# ClubNIKA.net
KiCad netlist of a schematic drawn in Altium Designer
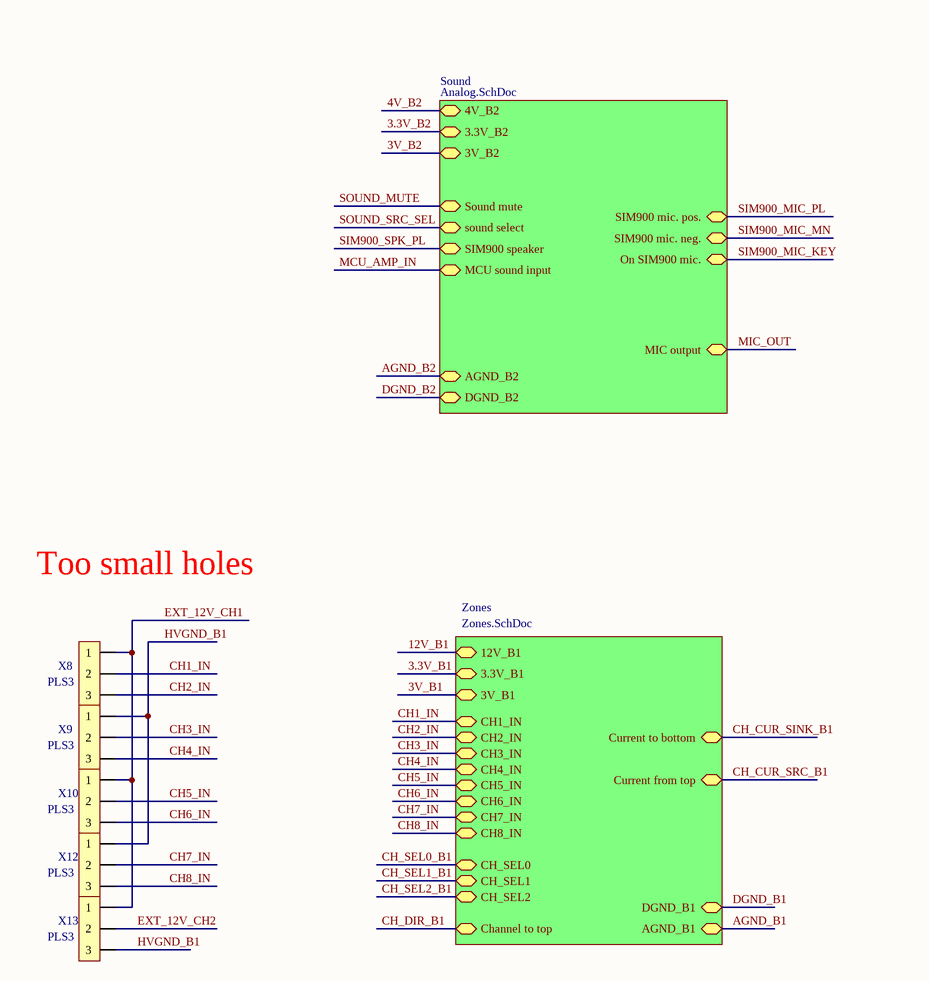
[diagram p0: ClubNIKA.SchDoc, top left]
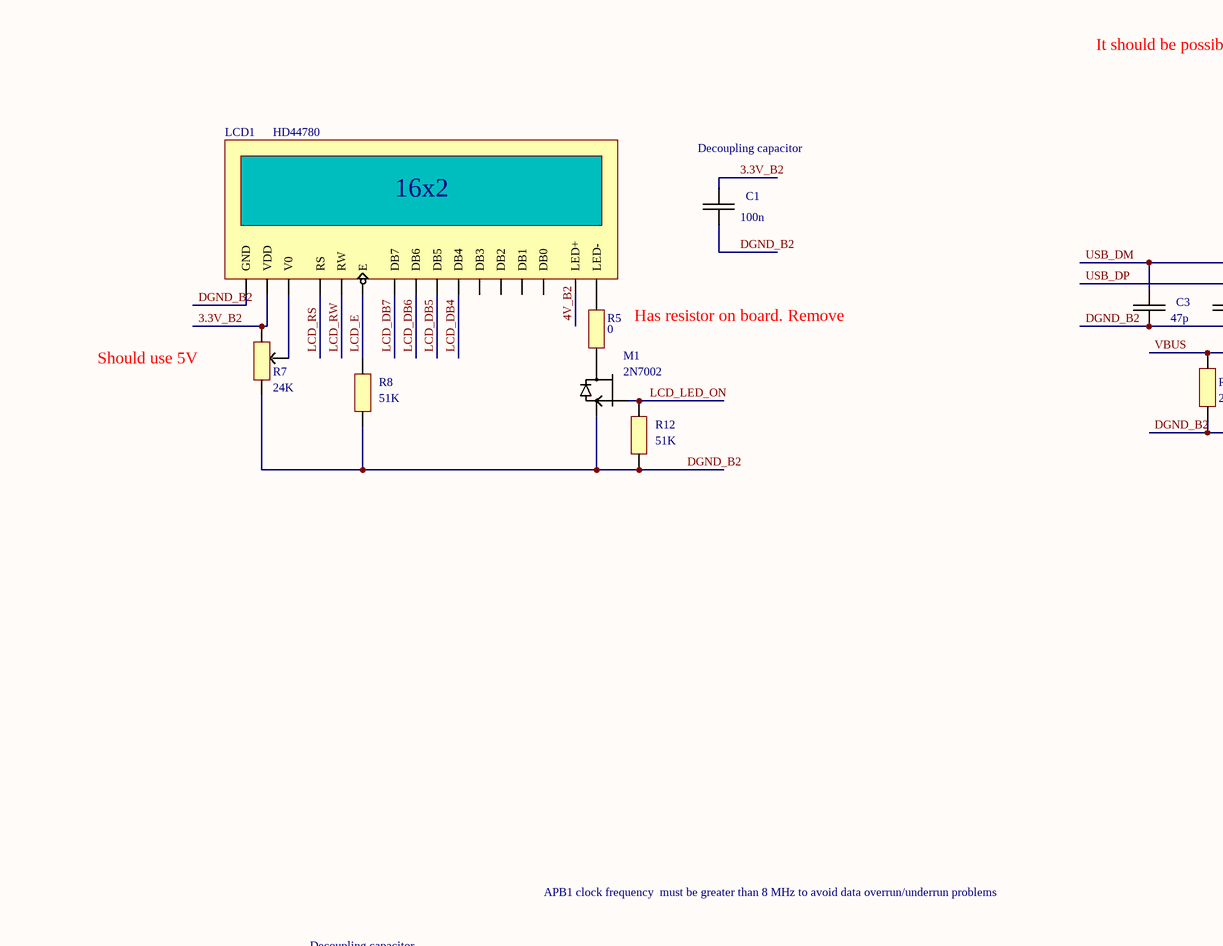
[diagram p1: ClubNIKA.SchDoc, top middle]
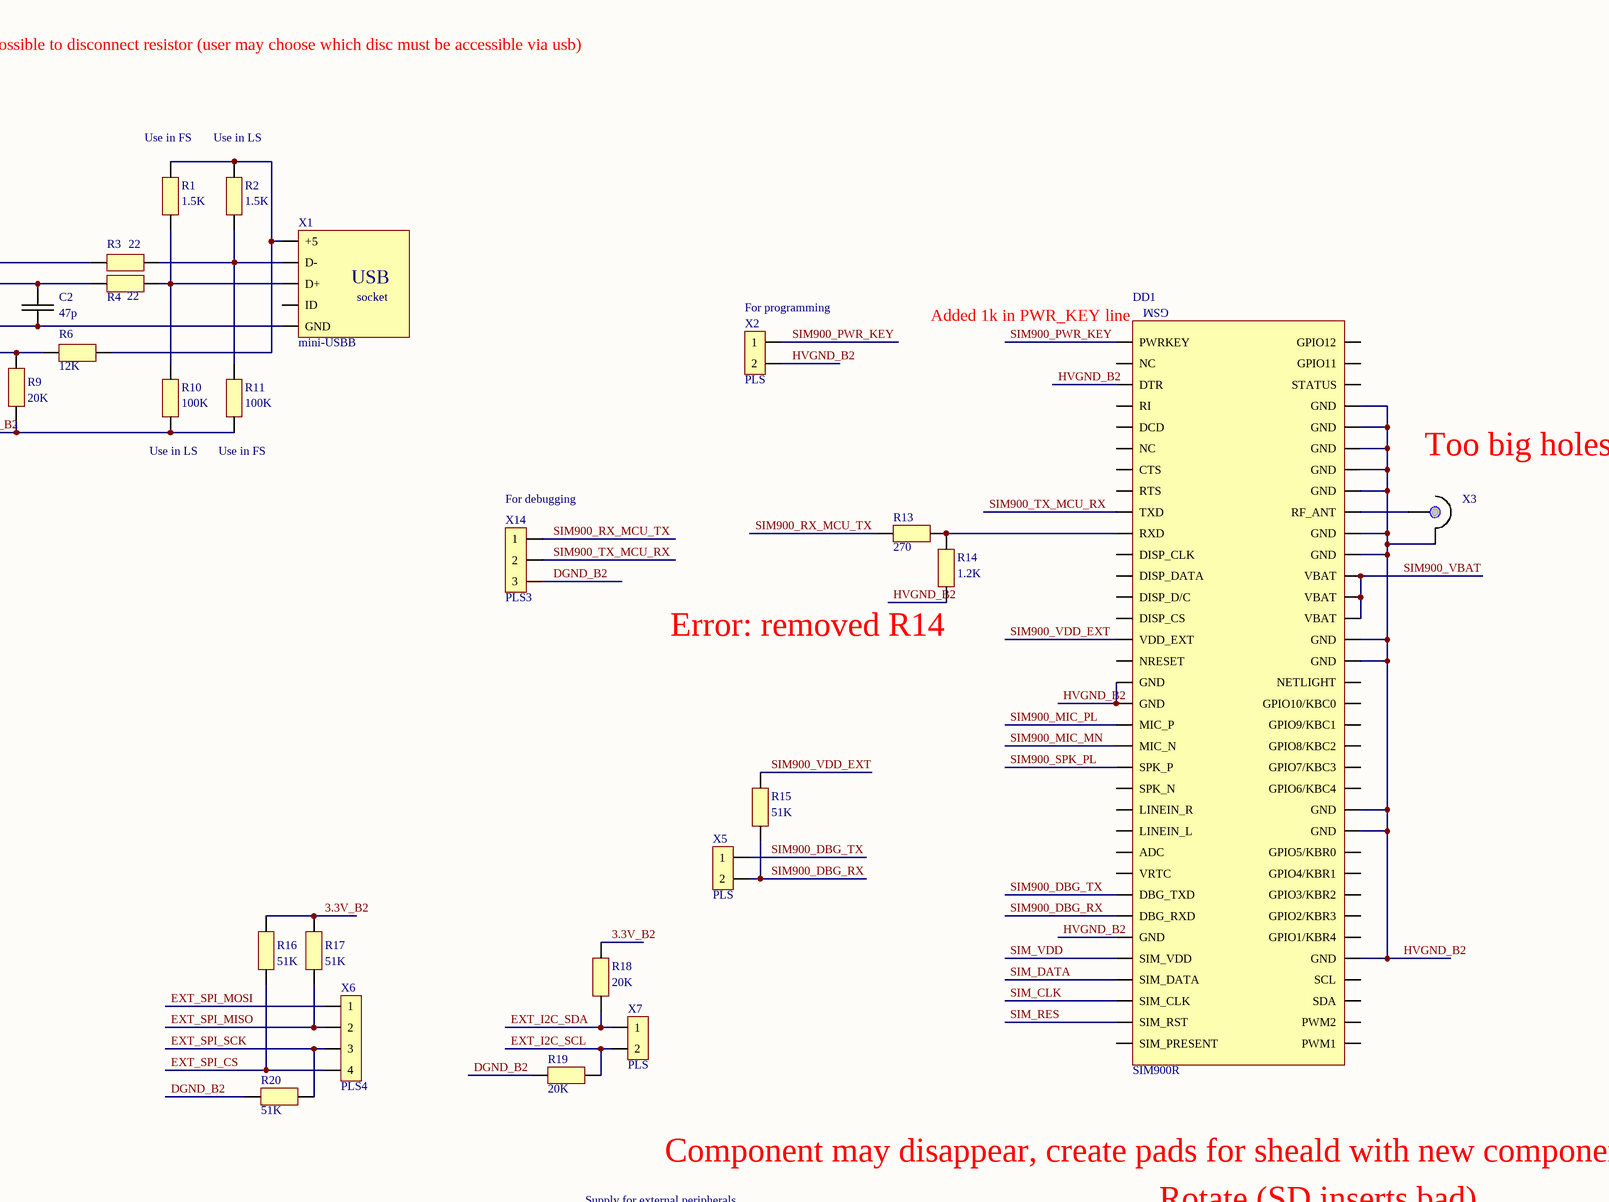
[diagram p2: ClubNIKA.SchDoc, top right]
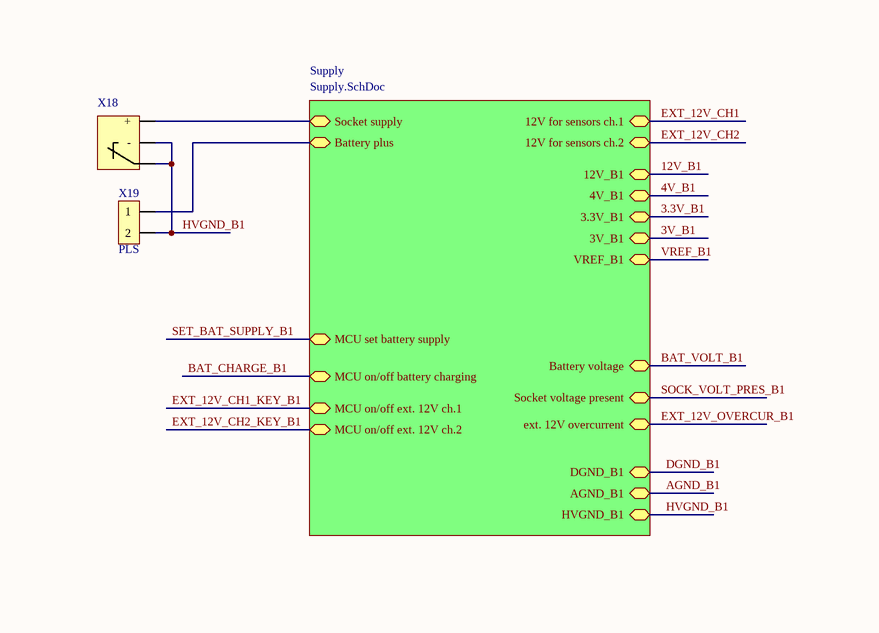
[diagram p3: ClubNIKA.SchDoc, bottom left]
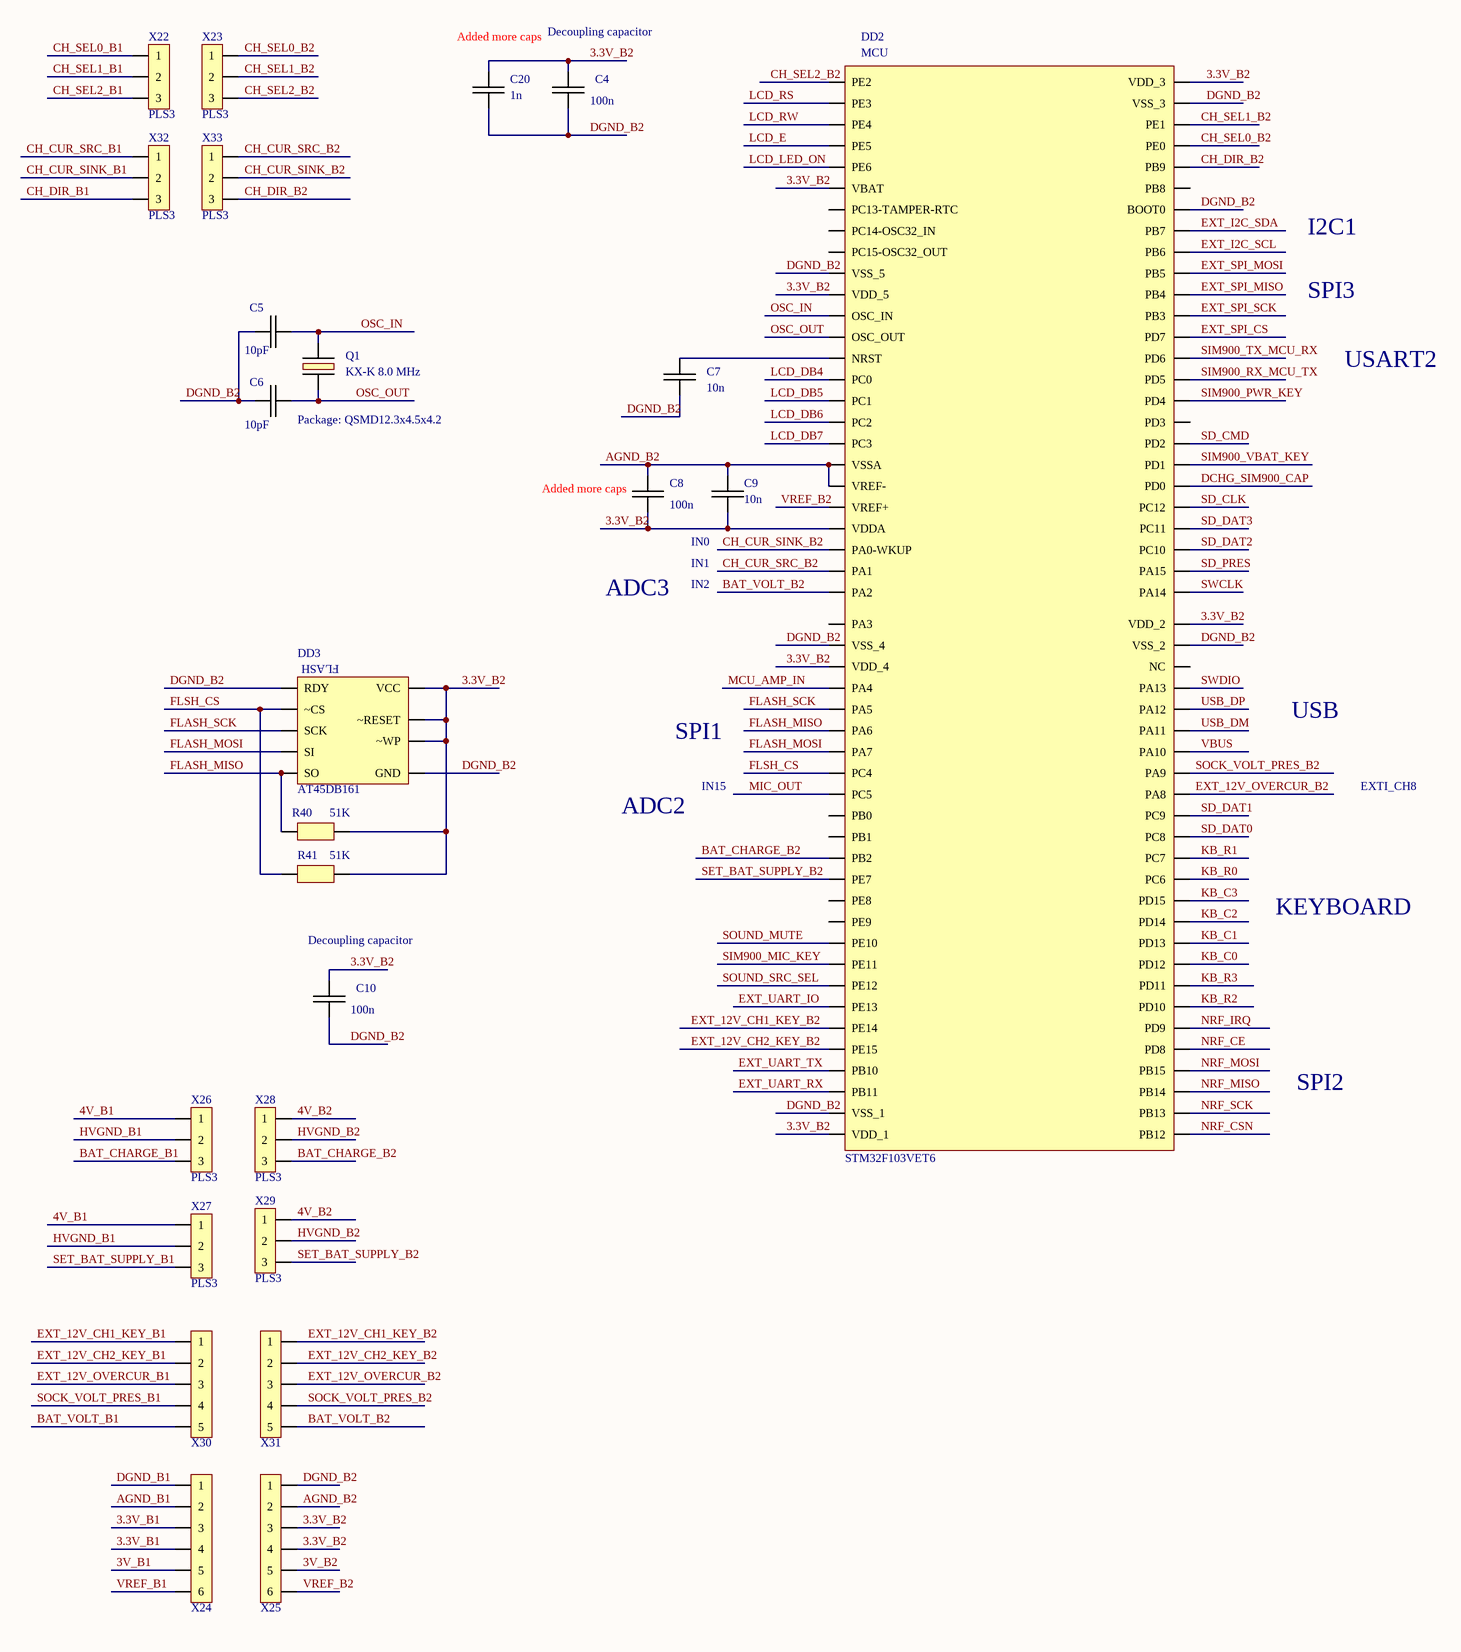
[diagram p4: ClubNIKA.SchDoc, bottom middle]
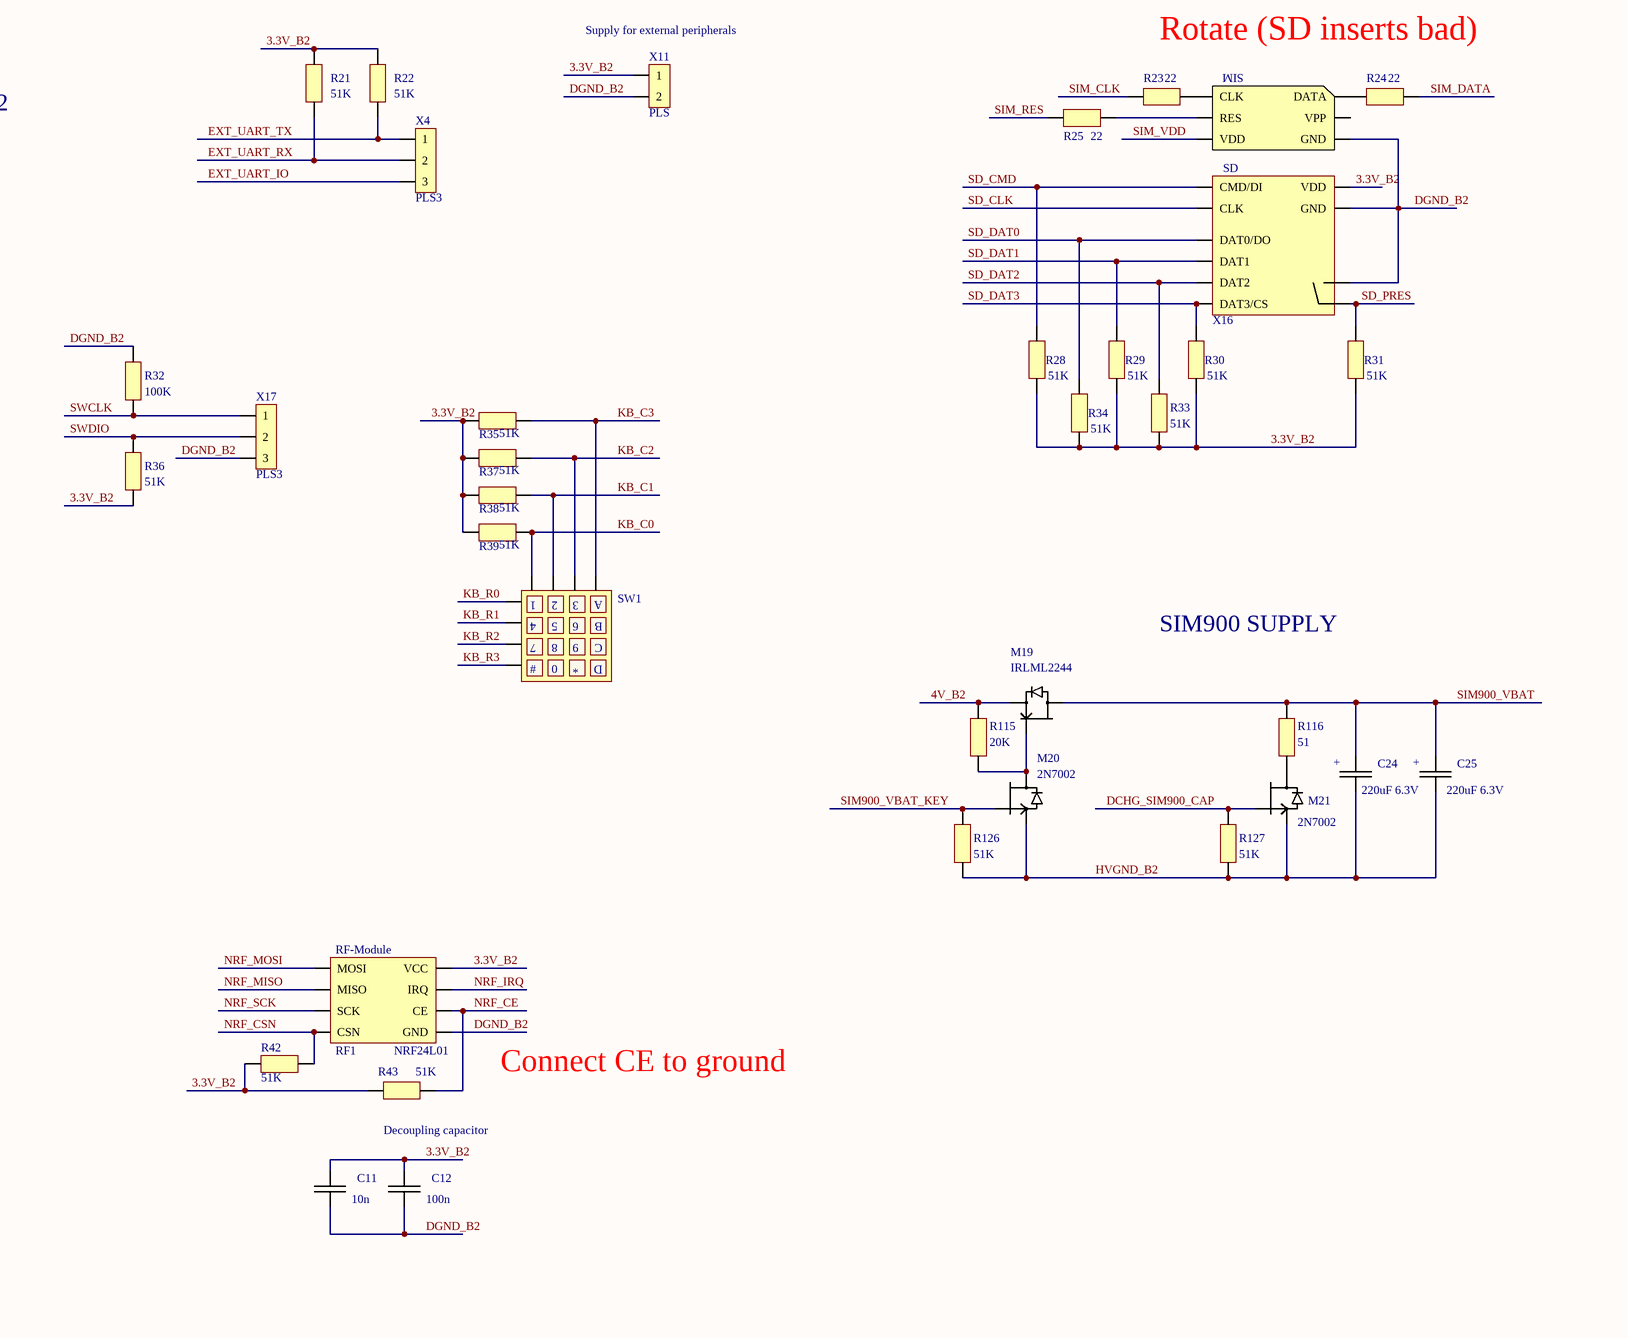
[diagram p5: ClubNIKA.SchDoc, bottom right]

(export (version "E")
  (design (tool "Eeschema 10.0.6"))
  (components
    (comp (ref "C1") (value "100n") (footprint "0805") (libsource (lib "PRIM_fact") (part "C")))
    (comp (ref "C2") (value "47p") (footprint "0805") (libsource (lib "PRIM_fact") (part "C")))
    (comp (ref "C3") (value "47p") (footprint "0805") (libsource (lib "PRIM_fact") (part "C")))
    (comp (ref "C4") (value "100n") (footprint "0805") (libsource (lib "PRIM_fact") (part "C")))
    (comp (ref "C5") (value "10pF") (footprint "0805") (libsource (lib "PRIM_fact") (part "C")))
    (comp (ref "C6") (value "10pF") (footprint "0805") (libsource (lib "PRIM_fact") (part "C")))
    (comp (ref "C7") (value "10n") (footprint "0805") (libsource (lib "PRIM_fact") (part "C")))
    (comp (ref "C8") (value "100n") (footprint "0805") (libsource (lib "PRIM_fact") (part "C")))
    (comp (ref "C9") (value "10n") (footprint "0805") (libsource (lib "PRIM_fact") (part "C")))
    (comp (ref "C10") (value "100n") (footprint "0805") (libsource (lib "PRIM_fact") (part "C")))
    (comp (ref "C11") (value "10n") (footprint "0805") (libsource (lib "PRIM_fact") (part "C")))
    (comp (ref "C12") (value "100n") (footprint "0805") (libsource (lib "PRIM_fact") (part "C")))
    (comp (ref "C20") (value "1n") (footprint "0805") (libsource (lib "PRIM_fact") (part "C")))
    (comp (ref "C24")
      (value "220uF 6.3V")
      (footprint "CALUM_THT_E5D13")
      (libsource (lib "PRIM_fact") (part "C_POL"))
    )
    (comp (ref "C25")
      (value "220uF 6.3V")
      (footprint "CALUM_THT_E5D13")
      (libsource (lib "PRIM_fact") (part "C_POL"))
    )
    (comp (ref "DD1") (value "SIM900R") (footprint "SIM900_R") (libsource (lib "IC_fact") (part "SIM900R")))
    (comp (ref "DD2")
      (value "STM32F103VET6")
      (footprint "QFP100")
      (libsource (lib "IC_fact") (part "STM32F103Vx"))
    )
    (comp (ref "DD3")
      (value "AT45DB161")
      (footprint "TSOP28")
      (libsource (lib "IC_fact") (part "AT45DB161/321"))
    )
    (comp (ref "LCD1")
      (value "HD44780")
      (footprint "LCD_HD44780_5")
      (libsource (lib "IC_fact") (part "LCD 16x2 HD44780"))
    )
    (comp (ref "M1") (value "2N7002") (footprint "SOT-23") (libsource (lib "PRIM_fact") (part "NMOS+DIODE")))
    (comp (ref "M19")
      (value "IRLML2244")
      (footprint "SOT-23")
      (libsource (lib "PRIM_fact") (part "PMOS+DIODE"))
    )
    (comp (ref "M20") (value "2N7002") (footprint "SOT-23") (libsource (lib "PRIM_fact") (part "NMOS+DIODE")))
    (comp (ref "M21") (value "2N7002") (footprint "SOT-23") (libsource (lib "PRIM_fact") (part "NMOS+DIODE")))
    (comp (ref "Q1")
      (value "KX-K 8.0 MHz")
      (footprint "OSC1_THT_10,8x4,5")
      (libsource (lib "PRIM_fact") (part "XTAL"))
    )
    (comp (ref "R1") (value "1.5K") (footprint "0805") (libsource (lib "PRIM_fact") (part "R")))
    (comp (ref "R2") (value "1.5K") (footprint "0805") (libsource (lib "PRIM_fact") (part "R")))
    (comp (ref "R3") (value "22") (footprint "0805") (libsource (lib "") (part "R_1")))
    (comp (ref "R4") (value "22") (footprint "0805") (libsource (lib "") (part "R_1")))
    (comp (ref "R5") (value "0") (footprint "1206") (libsource (lib "PRIM_fact") (part "R")))
    (comp (ref "R6") (value "12K") (footprint "0805") (libsource (lib "") (part "R_1")))
    (comp (ref "R7") (value "24K") (footprint "3305SMD(adj res)") (libsource (lib "PRIM_fact") (part "Radj")))
    (comp (ref "R8") (value "51K") (footprint "0805") (libsource (lib "PRIM_fact") (part "R")))
    (comp (ref "R9") (value "20K") (footprint "0805") (libsource (lib "PRIM_fact") (part "R")))
    (comp (ref "R10") (value "100K") (footprint "0805") (libsource (lib "PRIM_fact") (part "R")))
    (comp (ref "R11") (value "100K") (footprint "0805") (libsource (lib "PRIM_fact") (part "R")))
    (comp (ref "R12") (value "51K") (footprint "0805") (libsource (lib "PRIM_fact") (part "R")))
    (comp (ref "R13") (value "270") (footprint "0805") (libsource (lib "") (part "R_2")))
    (comp (ref "R14") (value "1.2K") (footprint "0805") (libsource (lib "PRIM_fact") (part "R")))
    (comp (ref "R15") (value "51K") (footprint "0805") (libsource (lib "PRIM_fact") (part "R")))
    (comp (ref "R16") (value "51K") (footprint "0805") (libsource (lib "PRIM_fact") (part "R")))
    (comp (ref "R17") (value "51K") (footprint "0805") (libsource (lib "PRIM_fact") (part "R")))
    (comp (ref "R18") (value "20K") (footprint "0805") (libsource (lib "PRIM_fact") (part "R")))
    (comp (ref "R19") (value "20K") (footprint "0805") (libsource (lib "") (part "R_2")))
    (comp (ref "R20") (value "51K") (footprint "0805") (libsource (lib "") (part "R_2")))
    (comp (ref "R21") (value "51K") (footprint "0805") (libsource (lib "PRIM_fact") (part "R")))
    (comp (ref "R22") (value "51K") (footprint "0805") (libsource (lib "PRIM_fact") (part "R")))
    (comp (ref "R23") (value "22") (footprint "0805") (libsource (lib "") (part "R_1")))
    (comp (ref "R24") (value "22") (footprint "0805") (libsource (lib "") (part "R_1")))
    (comp (ref "R25") (value "22") (footprint "0805") (libsource (lib "") (part "R_1")))
    (comp (ref "R28") (value "51K") (footprint "0805") (libsource (lib "PRIM_fact") (part "R")))
    (comp (ref "R29") (value "51K") (footprint "0805") (libsource (lib "PRIM_fact") (part "R")))
    (comp (ref "R30") (value "51K") (footprint "0805") (libsource (lib "PRIM_fact") (part "R")))
    (comp (ref "R31") (value "51K") (footprint "0805") (libsource (lib "PRIM_fact") (part "R")))
    (comp (ref "R32") (value "100K") (footprint "0805") (libsource (lib "PRIM_fact") (part "R")))
    (comp (ref "R33") (value "51K") (footprint "0805") (libsource (lib "PRIM_fact") (part "R")))
    (comp (ref "R34") (value "51K") (footprint "0805") (libsource (lib "PRIM_fact") (part "R")))
    (comp (ref "R35") (value "51K") (footprint "0805") (libsource (lib "") (part "R_1")))
    (comp (ref "R36") (value "51K") (footprint "0805") (libsource (lib "PRIM_fact") (part "R")))
    (comp (ref "R37") (value "51K") (footprint "0805") (libsource (lib "") (part "R_1")))
    (comp (ref "R38") (value "51K") (footprint "0805") (libsource (lib "") (part "R_1")))
    (comp (ref "R39") (value "51K") (footprint "0805") (libsource (lib "") (part "R_1")))
    (comp (ref "R40") (value "51K") (footprint "0805") (libsource (lib "") (part "R_2")))
    (comp (ref "R41") (value "51K") (footprint "0805") (libsource (lib "") (part "R_2")))
    (comp (ref "R42") (value "51K") (footprint "0805") (libsource (lib "") (part "R_2")))
    (comp (ref "R43") (value "51K") (footprint "0805") (libsource (lib "") (part "R_1")))
    (comp (ref "R115") (value "20K") (footprint "0805") (libsource (lib "PRIM_fact") (part "R")))
    (comp (ref "R116") (value "51") (footprint "0805") (libsource (lib "PRIM_fact") (part "R")))
    (comp (ref "R126") (value "51K") (footprint "0805") (libsource (lib "") (part "R_1")))
    (comp (ref "R127") (value "51K") (footprint "0805") (libsource (lib "") (part "R_1")))
    (comp (ref "RF1")
      (value "NRF24L01")
      (footprint "NRF24L01_MOD_ANGLE")
      (libsource (lib "IC_fact") (part "NRF24L01"))
    )
    (comp (ref "SW1")
      (value "KEYBOARD4x4")
      (footprint "KEYBOURD_4x4_1")
      (libsource (lib "PRIM_fact") (part "KEYBOARD4x4"))
    )
    (comp (ref "X1")
      (value "mini-USBB")
      (footprint "MINI_USBA_FEMALE")
      (libsource (lib "PRIM_fact") (part "MINI_USB_FEMALE"))
    )
    (comp (ref "X2") (value "PLS") (footprint "PLS_2") (libsource (lib "") (part "CONT_2_1")))
    (comp (ref "X3")
      (value "SMA_FEMALE")
      (footprint "SMA_FEMALE")
      (libsource (lib "PRIM_fact") (part "SMA_FEMALE"))
    )
    (comp (ref "X4") (value "PLS3") (footprint "PLS_3") (libsource (lib "PRIM_fact") (part "CONT_3")))
    (comp (ref "X5") (value "PLS") (footprint "PLS_2") (libsource (lib "") (part "CONT_2_1")))
    (comp (ref "X6") (value "PLS4") (footprint "PLS_4") (libsource (lib "PRIM_fact") (part "CONT_4")))
    (comp (ref "X7") (value "PLS") (footprint "PLS_2") (libsource (lib "PRIM_fact") (part "CONT_2")))
    (comp (ref "X8")
      (value "PLS3")
      (footprint "TERMINALS_7.7x15.5(step 5mm)")
      (libsource (lib "") (part "CONT_3_1"))
    )
    (comp (ref "X9")
      (value "PLS3")
      (footprint "TERMINALS_7.7x15.5(step 5mm)")
      (libsource (lib "") (part "CONT_3_1"))
    )
    (comp (ref "X10")
      (value "PLS3")
      (footprint "TERMINALS_7.7x15.5(step 5mm)")
      (libsource (lib "") (part "CONT_3_1"))
    )
    (comp (ref "X11") (value "PLS") (footprint "PLS_2") (libsource (lib "PRIM_fact") (part "CONT_2")))
    (comp (ref "X12")
      (value "PLS3")
      (footprint "TERMINALS_7.7x15.5(step 5mm)")
      (libsource (lib "") (part "CONT_3_1"))
    )
    (comp (ref "X13")
      (value "PLS3")
      (footprint "TERMINALS_7.7x15.5(step 5mm)")
      (libsource (lib "") (part "CONT_3_1"))
    )
    (comp (ref "X14") (value "PLS3") (footprint "PLS_3") (libsource (lib "") (part "CONT_3_1")))
    (comp (ref "X16")
      (value "SIM_SD_HOLDER1")
      (footprint "SIM_SD_HOLDER1")
      (libsource (lib "PRIM_fact") (part "SIM_SD_HOLDER1"))
    )
    (comp (ref "X17") (value "PLS3") (footprint "PLS_3") (libsource (lib "PRIM_fact") (part "CONT_3")))
    (comp (ref "X18")
      (value "SUPPLY_1")
      (footprint "SUP_SOCK_D5.5D1.8")
      (libsource (lib "PRIM_fact") (part "SUPPLY_1"))
    )
    (comp (ref "X19") (value "PLS") (footprint "PLS_2") (libsource (lib "") (part "CONT_2_1")))
    (comp (ref "X22") (value "PLS3") (footprint "PLS_3") (libsource (lib "PRIM_fact") (part "CONT_3")))
    (comp (ref "X23") (value "PLS3") (footprint "PLS_3") (libsource (lib "") (part "CONT_3_1")))
    (comp (ref "X24") (value "PLS6") (footprint "PLS_6") (libsource (lib "") (part "CONT_6_1")))
    (comp (ref "X25") (value "PLS6") (footprint "PLS_6") (libsource (lib "PRIM_fact") (part "CONT_6")))
    (comp (ref "X26") (value "PLS3") (footprint "PLS_3") (libsource (lib "PRIM_fact") (part "CONT_3")))
    (comp (ref "X27") (value "PLS3") (footprint "PLS_3") (libsource (lib "PRIM_fact") (part "CONT_3")))
    (comp (ref "X28") (value "PLS3") (footprint "PLS_3") (libsource (lib "") (part "CONT_3_1")))
    (comp (ref "X29") (value "PLS3") (footprint "PLS_3") (libsource (lib "") (part "CONT_3_1")))
    (comp (ref "X30") (value "CONT_5") (footprint "PLS_5") (libsource (lib "") (part "CONT_5_1")))
    (comp (ref "X31") (value "CONT_5") (footprint "PLS_5") (libsource (lib "PRIM_fact") (part "CONT_5")))
    (comp (ref "X32") (value "PLS3") (footprint "PLS_3") (libsource (lib "PRIM_fact") (part "CONT_3")))
    (comp (ref "X33") (value "PLS3") (footprint "PLS_3") (libsource (lib "") (part "CONT_3_1")))
  )
  (nets
    (net (code "1") (name "/3.3V_B1") (class "Default")
      (node (ref "X24") (pin "3") (pinfunction "3_3") (pintype "passive"))
      (node (ref "X24") (pin "4") (pinfunction "4_4") (pintype "passive"))
    )
    (net (code "2") (name "/3.3V_B2") (class "Default")
      (node (ref "C1") (pin "2") (pintype "passive"))
      (node (ref "C10") (pin "2") (pintype "passive"))
      (node (ref "C11") (pin "2") (pintype "passive"))
      (node (ref "C12") (pin "2") (pintype "passive"))
      (node (ref "C20") (pin "2") (pintype "passive"))
      (node (ref "C4") (pin "2") (pintype "passive"))
      (node (ref "C8") (pin "1") (pintype "passive"))
      (node (ref "C9") (pin "1") (pintype "passive"))
      (node (ref "DD2") (pin "100") (pinfunction "VDD_3_100") (pintype "passive"))
      (node (ref "DD2") (pin "11") (pinfunction "VDD_5_11") (pintype "passive"))
      (node (ref "DD2") (pin "22") (pinfunction "VDDA_22") (pintype "passive"))
      (node (ref "DD2") (pin "28") (pinfunction "VDD_4_28") (pintype "passive"))
      (node (ref "DD2") (pin "50") (pinfunction "VDD_1_50") (pintype "passive"))
      (node (ref "DD2") (pin "6") (pinfunction "VBAT_6") (pintype "passive"))
      (node (ref "DD2") (pin "75") (pinfunction "VDD_2_75") (pintype "passive"))
      (node (ref "DD3") (pin "2") (pinfunction "~RESET_2") (pintype "passive"))
      (node (ref "DD3") (pin "3") (pinfunction "~WP_3") (pintype "passive"))
      (node (ref "DD3") (pin "6") (pinfunction "VCC_6") (pintype "passive"))
      (node (ref "LCD1") (pin "VDD") (pinfunction "VDD_VDD") (pintype "passive"))
      (node (ref "R16") (pin "1") (pintype "passive"))
      (node (ref "R17") (pin "1") (pintype "passive"))
      (node (ref "R18") (pin "1") (pintype "passive"))
      (node (ref "R21") (pin "1") (pintype "passive"))
      (node (ref "R22") (pin "1") (pintype "passive"))
      (node (ref "R28") (pin "2") (pintype "passive"))
      (node (ref "R29") (pin "2") (pintype "passive"))
      (node (ref "R30") (pin "2") (pintype "passive"))
      (node (ref "R31") (pin "2") (pintype "passive"))
      (node (ref "R33") (pin "2") (pintype "passive"))
      (node (ref "R34") (pin "2") (pintype "passive"))
      (node (ref "R35") (pin "2") (pintype "passive"))
      (node (ref "R36") (pin "2") (pintype "passive"))
      (node (ref "R37") (pin "2") (pintype "passive"))
      (node (ref "R38") (pin "2") (pintype "passive"))
      (node (ref "R39") (pin "2") (pintype "passive"))
      (node (ref "R40") (pin "2") (pintype "passive"))
      (node (ref "R41") (pin "2") (pintype "passive"))
      (node (ref "R42") (pin "1") (pintype "passive"))
      (node (ref "R43") (pin "2") (pintype "passive"))
      (node (ref "R7") (pin "1") (pintype "passive"))
      (node (ref "RF1") (pin "2") (pinfunction "VCC_2") (pintype "passive"))
      (node (ref "X11") (pin "1") (pinfunction "1_1") (pintype "passive"))
      (node (ref "X16") (pin "SD_VDD") (pinfunction "VDD_SD_VDD") (pintype "passive"))
      (node (ref "X25") (pin "3") (pinfunction "3_3") (pintype "passive"))
      (node (ref "X25") (pin "4") (pinfunction "4_4") (pintype "passive"))
    )
    (net (code "3") (name "/3V_B1") (class "Default")
      (node (ref "X24") (pin "5") (pinfunction "5_5") (pintype "passive"))
    )
    (net (code "4") (name "/3V_B2") (class "Default")
      (node (ref "X25") (pin "5") (pinfunction "5_5") (pintype "passive"))
    )
    (net (code "5") (name "/4V_B1") (class "Default")
      (node (ref "X26") (pin "1") (pinfunction "1_1") (pintype "passive"))
      (node (ref "X27") (pin "1") (pinfunction "1_1") (pintype "passive"))
    )
    (net (code "6") (name "/4V_B2") (class "Default")
      (node (ref "LCD1") (pin "LED+") (pinfunction "LED+_LED+") (pintype "passive"))
      (node (ref "M19") (pin "2") (pintype "passive"))
      (node (ref "R115") (pin "1") (pintype "passive"))
      (node (ref "X28") (pin "1") (pinfunction "1_1") (pintype "passive"))
      (node (ref "X29") (pin "1") (pinfunction "1_1") (pintype "passive"))
    )
    (net (code "8") (name "/AGND_B1") (class "Default")
      (node (ref "X24") (pin "2") (pinfunction "2_2") (pintype "passive"))
    )
    (net (code "9") (name "/AGND_B2") (class "Default")
      (node (ref "C8") (pin "2") (pintype "passive"))
      (node (ref "C9") (pin "2") (pintype "passive"))
      (node (ref "DD2") (pin "19") (pinfunction "VSSA_19") (pintype "passive"))
      (node (ref "DD2") (pin "20") (pinfunction "VREF-_20") (pintype "passive"))
      (node (ref "X25") (pin "2") (pinfunction "2_2") (pintype "passive"))
    )
    (net (code "10") (name "/BAT_CHARGE_B1") (class "Default")
      (node (ref "X26") (pin "3") (pinfunction "3_3") (pintype "passive"))
    )
    (net (code "11") (name "/BAT_CHARGE_B2") (class "Default")
      (node (ref "DD2") (pin "37") (pinfunction "PB2_37") (pintype "passive"))
      (node (ref "X28") (pin "3") (pinfunction "3_3") (pintype "passive"))
    )
    (net (code "12") (name "/BAT_VOLT_B1") (class "Default")
      (node (ref "X30") (pin "5") (pinfunction "5_5") (pintype "passive"))
    )
    (net (code "13") (name "/BAT_VOLT_B2") (class "Default")
      (node (ref "DD2") (pin "25") (pinfunction "PA2_25") (pintype "passive"))
      (node (ref "X31") (pin "5") (pinfunction "5_5") (pintype "passive"))
    )
    (net (code "14") (name "/Battery plus") (class "Default")
      (node (ref "X19") (pin "1") (pinfunction "1_1") (pintype "passive"))
    )
    (net (code "15") (name "/CH1_IN") (class "Default")
      (node (ref "X8") (pin "2") (pinfunction "2_2") (pintype "passive"))
    )
    (net (code "16") (name "/CH2_IN") (class "Default")
      (node (ref "X8") (pin "3") (pinfunction "3_3") (pintype "passive"))
    )
    (net (code "17") (name "/CH3_IN") (class "Default")
      (node (ref "X9") (pin "2") (pinfunction "2_2") (pintype "passive"))
    )
    (net (code "18") (name "/CH4_IN") (class "Default")
      (node (ref "X9") (pin "3") (pinfunction "3_3") (pintype "passive"))
    )
    (net (code "19") (name "/CH5_IN") (class "Default")
      (node (ref "X10") (pin "2") (pinfunction "2_2") (pintype "passive"))
    )
    (net (code "20") (name "/CH6_IN") (class "Default")
      (node (ref "X10") (pin "3") (pinfunction "3_3") (pintype "passive"))
    )
    (net (code "21") (name "/CH7_IN") (class "Default")
      (node (ref "X12") (pin "2") (pinfunction "2_2") (pintype "passive"))
    )
    (net (code "22") (name "/CH8_IN") (class "Default")
      (node (ref "X12") (pin "3") (pinfunction "3_3") (pintype "passive"))
    )
    (net (code "23") (name "/CH_CUR_SINK_B1") (class "Default")
      (node (ref "X32") (pin "2") (pinfunction "2_2") (pintype "passive"))
    )
    (net (code "24") (name "/CH_CUR_SINK_B2") (class "Default")
      (node (ref "DD2") (pin "23") (pinfunction "PA0-WKUP_23") (pintype "passive"))
      (node (ref "X33") (pin "2") (pinfunction "2_2") (pintype "passive"))
    )
    (net (code "25") (name "/CH_CUR_SRC_B1") (class "Default")
      (node (ref "X32") (pin "1") (pinfunction "1_1") (pintype "passive"))
    )
    (net (code "26") (name "/CH_CUR_SRC_B2") (class "Default")
      (node (ref "DD2") (pin "24") (pinfunction "PA1_24") (pintype "passive"))
      (node (ref "X33") (pin "1") (pinfunction "1_1") (pintype "passive"))
    )
    (net (code "27") (name "/CH_DIR_B1") (class "Default")
      (node (ref "X32") (pin "3") (pinfunction "3_3") (pintype "passive"))
    )
    (net (code "28") (name "/CH_DIR_B2") (class "Default")
      (node (ref "DD2") (pin "96") (pinfunction "PB9_96") (pintype "passive"))
      (node (ref "X33") (pin "3") (pinfunction "3_3") (pintype "passive"))
    )
    (net (code "29") (name "/CH_SEL0_B1") (class "Default")
      (node (ref "X22") (pin "1") (pinfunction "1_1") (pintype "passive"))
    )
    (net (code "30") (name "/CH_SEL0_B2") (class "Default")
      (node (ref "DD2") (pin "97") (pinfunction "PE0_97") (pintype "passive"))
      (node (ref "X23") (pin "1") (pinfunction "1_1") (pintype "passive"))
    )
    (net (code "31") (name "/CH_SEL1_B1") (class "Default")
      (node (ref "X22") (pin "2") (pinfunction "2_2") (pintype "passive"))
    )
    (net (code "32") (name "/CH_SEL1_B2") (class "Default")
      (node (ref "DD2") (pin "98") (pinfunction "PE1_98") (pintype "passive"))
      (node (ref "X23") (pin "2") (pinfunction "2_2") (pintype "passive"))
    )
    (net (code "33") (name "/CH_SEL2_B1") (class "Default")
      (node (ref "X22") (pin "3") (pinfunction "3_3") (pintype "passive"))
    )
    (net (code "34") (name "/CH_SEL2_B2") (class "Default")
      (node (ref "DD2") (pin "1") (pinfunction "PE2_1") (pintype "passive"))
      (node (ref "X23") (pin "3") (pinfunction "3_3") (pintype "passive"))
    )
    (net (code "35") (name "/DCHG_SIM900_CAP") (class "Default")
      (node (ref "DD2") (pin "81") (pinfunction "PD0_81") (pintype "passive"))
      (node (ref "M21") (pin "1") (pintype "passive"))
      (node (ref "R127") (pin "1") (pintype "passive"))
    )
    (net (code "36") (name "/DGND_B1") (class "Default")
      (node (ref "X24") (pin "1") (pinfunction "1_1") (pintype "passive"))
    )
    (net (code "37") (name "/DGND_B2") (class "Default")
      (node (ref "C1") (pin "1") (pintype "passive"))
      (node (ref "C10") (pin "1") (pintype "passive"))
      (node (ref "C11") (pin "1") (pintype "passive"))
      (node (ref "C12") (pin "1") (pintype "passive"))
      (node (ref "C2") (pin "1") (pintype "passive"))
      (node (ref "C20") (pin "1") (pintype "passive"))
      (node (ref "C3") (pin "1") (pintype "passive"))
      (node (ref "C4") (pin "1") (pintype "passive"))
      (node (ref "C5") (pin "1") (pintype "passive"))
      (node (ref "C6") (pin "1") (pintype "passive"))
      (node (ref "C7") (pin "1") (pintype "passive"))
      (node (ref "DD2") (pin "10") (pinfunction "VSS_5_10") (pintype "passive"))
      (node (ref "DD2") (pin "27") (pinfunction "VSS_4_27") (pintype "passive"))
      (node (ref "DD2") (pin "49") (pinfunction "VSS_1_49") (pintype "passive"))
      (node (ref "DD2") (pin "74") (pinfunction "VSS_2_74") (pintype "passive"))
      (node (ref "DD2") (pin "94") (pinfunction "BOOT0_94") (pintype "passive"))
      (node (ref "DD2") (pin "99") (pinfunction "VSS_3_99") (pintype "passive"))
      (node (ref "DD3") (pin "1") (pinfunction "RDY_1") (pintype "passive"))
      (node (ref "DD3") (pin "7") (pinfunction "GND_7") (pintype "passive"))
      (node (ref "LCD1") (pin "GND") (pinfunction "GND_GND") (pintype "passive"))
      (node (ref "M1") (pin "2") (pintype "passive"))
      (node (ref "R10") (pin "2") (pintype "passive"))
      (node (ref "R11") (pin "2") (pintype "passive"))
      (node (ref "R12") (pin "2") (pintype "passive"))
      (node (ref "R19") (pin "1") (pintype "passive"))
      (node (ref "R20") (pin "1") (pintype "passive"))
      (node (ref "R32") (pin "1") (pintype "passive"))
      (node (ref "R7") (pin "2") (pintype "passive"))
      (node (ref "R8") (pin "2") (pintype "passive"))
      (node (ref "R9") (pin "2") (pintype "passive"))
      (node (ref "RF1") (pin "1") (pinfunction "GND_1") (pintype "passive"))
      (node (ref "X1") (pin "GND") (pinfunction "GND_GND") (pintype "passive"))
      (node (ref "X11") (pin "2") (pinfunction "2_2") (pintype "passive"))
      (node (ref "X14") (pin "3") (pinfunction "3_3") (pintype "passive"))
      (node (ref "X16") (pin "SD_GND") (pinfunction "GND_SD_GND") (pintype "passive"))
      (node (ref "X16") (pin "SD_PRES1") (pintype "passive"))
      (node (ref "X16") (pin "SIM_GND") (pinfunction "GND_SIM_GND") (pintype "passive"))
      (node (ref "X17") (pin "3") (pinfunction "3_3") (pintype "passive"))
      (node (ref "X25") (pin "1") (pinfunction "1_1") (pintype "passive"))
    )
    (net (code "38") (name "/EXT_12V_CH1") (class "Default")
      (node (ref "X10") (pin "1") (pinfunction "1_1") (pintype "passive"))
      (node (ref "X13") (pin "1") (pinfunction "1_1") (pintype "passive"))
      (node (ref "X8") (pin "1") (pinfunction "1_1") (pintype "passive"))
    )
    (net (code "39") (name "/EXT_12V_CH1_KEY_B1") (class "Default")
      (node (ref "X30") (pin "1") (pinfunction "1_1") (pintype "passive"))
    )
    (net (code "40") (name "/EXT_12V_CH1_KEY_B2") (class "Default")
      (node (ref "DD2") (pin "45") (pinfunction "PE14_45") (pintype "passive"))
      (node (ref "X31") (pin "1") (pinfunction "1_1") (pintype "passive"))
    )
    (net (code "41") (name "/EXT_12V_CH2") (class "Default")
      (node (ref "X13") (pin "2") (pinfunction "2_2") (pintype "passive"))
    )
    (net (code "42") (name "/EXT_12V_CH2_KEY_B1") (class "Default")
      (node (ref "X30") (pin "2") (pinfunction "2_2") (pintype "passive"))
    )
    (net (code "43") (name "/EXT_12V_CH2_KEY_B2") (class "Default")
      (node (ref "DD2") (pin "46") (pinfunction "PE15_46") (pintype "passive"))
      (node (ref "X31") (pin "2") (pinfunction "2_2") (pintype "passive"))
    )
    (net (code "44") (name "/EXT_12V_OVERCUR_B1") (class "Default")
      (node (ref "X30") (pin "3") (pinfunction "3_3") (pintype "passive"))
    )
    (net (code "45") (name "/EXT_12V_OVERCUR_B2") (class "Default")
      (node (ref "DD2") (pin "67") (pinfunction "PA8_67") (pintype "passive"))
      (node (ref "X31") (pin "3") (pinfunction "3_3") (pintype "passive"))
    )
    (net (code "46") (name "/EXT_I2C_SCL") (class "Default")
      (node (ref "DD2") (pin "92") (pinfunction "PB6_92") (pintype "passive"))
      (node (ref "R19") (pin "2") (pintype "passive"))
      (node (ref "X7") (pin "2") (pinfunction "2_2") (pintype "passive"))
    )
    (net (code "47") (name "/EXT_I2C_SDA") (class "Default")
      (node (ref "DD2") (pin "93") (pinfunction "PB7_93") (pintype "passive"))
      (node (ref "R18") (pin "2") (pintype "passive"))
      (node (ref "X7") (pin "1") (pinfunction "1_1") (pintype "passive"))
    )
    (net (code "48") (name "/EXT_SPI_CS") (class "Default")
      (node (ref "DD2") (pin "88") (pinfunction "PD7_88") (pintype "passive"))
      (node (ref "R16") (pin "2") (pintype "passive"))
      (node (ref "X6") (pin "4") (pinfunction "4_4") (pintype "passive"))
    )
    (net (code "49") (name "/EXT_SPI_MISO") (class "Default")
      (node (ref "DD2") (pin "90") (pinfunction "PB4_90") (pintype "passive"))
      (node (ref "R17") (pin "2") (pintype "passive"))
      (node (ref "X6") (pin "2") (pinfunction "2_2") (pintype "passive"))
    )
    (net (code "50") (name "/EXT_SPI_MOSI") (class "Default")
      (node (ref "DD2") (pin "91") (pinfunction "PB5_91") (pintype "passive"))
      (node (ref "X6") (pin "1") (pinfunction "1_1") (pintype "passive"))
    )
    (net (code "51") (name "/EXT_SPI_SCK") (class "Default")
      (node (ref "DD2") (pin "89") (pinfunction "PB3_89") (pintype "passive"))
      (node (ref "R20") (pin "2") (pintype "passive"))
      (node (ref "X6") (pin "3") (pinfunction "3_3") (pintype "passive"))
    )
    (net (code "52") (name "/EXT_UART_IO") (class "Default")
      (node (ref "DD2") (pin "44") (pinfunction "PE13_44") (pintype "passive"))
      (node (ref "X4") (pin "3") (pinfunction "3_3") (pintype "passive"))
    )
    (net (code "53") (name "/EXT_UART_RX") (class "Default")
      (node (ref "DD2") (pin "48") (pinfunction "PB11_48") (pintype "passive"))
      (node (ref "R21") (pin "2") (pintype "passive"))
      (node (ref "X4") (pin "2") (pinfunction "2_2") (pintype "passive"))
    )
    (net (code "54") (name "/EXT_UART_TX") (class "Default")
      (node (ref "DD2") (pin "47") (pinfunction "PB10_47") (pintype "passive"))
      (node (ref "R22") (pin "2") (pintype "passive"))
      (node (ref "X4") (pin "1") (pinfunction "1_1") (pintype "passive"))
    )
    (net (code "55") (name "/FLASH_MISO") (class "Default")
      (node (ref "DD2") (pin "31") (pinfunction "PA6_31") (pintype "passive"))
      (node (ref "DD3") (pin "14") (pinfunction "SO_14") (pintype "passive"))
      (node (ref "R40") (pin "1") (pintype "passive"))
    )
    (net (code "56") (name "/FLASH_MOSI") (class "Default")
      (node (ref "DD2") (pin "32") (pinfunction "PA7_32") (pintype "passive"))
      (node (ref "DD3") (pin "13") (pinfunction "SI_13") (pintype "passive"))
    )
    (net (code "57") (name "/FLASH_SCK") (class "Default")
      (node (ref "DD2") (pin "30") (pinfunction "PA5_30") (pintype "passive"))
      (node (ref "DD3") (pin "12") (pinfunction "SCK_12") (pintype "passive"))
    )
    (net (code "58") (name "/FLSH_CS") (class "Default")
      (node (ref "DD2") (pin "33") (pinfunction "PC4_33") (pintype "passive"))
      (node (ref "DD3") (pin "11") (pinfunction "~CS_11") (pintype "passive"))
      (node (ref "R41") (pin "1") (pintype "passive"))
    )
    (net (code "59") (name "/HVGND_B1") (class "Default")
      (node (ref "X12") (pin "1") (pinfunction "1_1") (pintype "passive"))
      (node (ref "X13") (pin "3") (pinfunction "3_3") (pintype "passive"))
      (node (ref "X18") (pin "-") (pinfunction "-_-") (pintype "passive"))
      (node (ref "X18") (pin "PRES") (pintype "passive"))
      (node (ref "X19") (pin "2") (pinfunction "2_2") (pintype "passive"))
      (node (ref "X26") (pin "2") (pinfunction "2_2") (pintype "passive"))
      (node (ref "X27") (pin "2") (pinfunction "2_2") (pintype "passive"))
      (node (ref "X9") (pin "1") (pinfunction "1_1") (pintype "passive"))
    )
    (net (code "60") (name "/HVGND_B2") (class "Default")
      (node (ref "C24") (pin "2") (pintype "passive"))
      (node (ref "C25") (pin "2") (pintype "passive"))
      (node (ref "DD1") (pin "17") (pinfunction "GND_17") (pintype "passive"))
      (node (ref "DD1") (pin "18") (pinfunction "GND_18") (pintype "passive"))
      (node (ref "DD1") (pin "29") (pinfunction "GND_29") (pintype "passive"))
      (node (ref "DD1") (pin "3") (pinfunction "DTR_3") (pintype "passive"))
      (node (ref "DD1") (pin "39") (pinfunction "GND_39") (pintype "passive"))
      (node (ref "DD1") (pin "45") (pinfunction "GND_45") (pintype "passive"))
      (node (ref "DD1") (pin "46") (pinfunction "GND_46") (pintype "passive"))
      (node (ref "DD1") (pin "53") (pinfunction "GND_53") (pintype "passive"))
      (node (ref "DD1") (pin "54") (pinfunction "GND_54") (pintype "passive"))
      (node (ref "DD1") (pin "58") (pinfunction "GND_58") (pintype "passive"))
      (node (ref "DD1") (pin "59") (pinfunction "GND_59") (pintype "passive"))
      (node (ref "DD1") (pin "61") (pinfunction "GND_61") (pintype "passive"))
      (node (ref "DD1") (pin "62") (pinfunction "GND_62") (pintype "passive"))
      (node (ref "DD1") (pin "63") (pinfunction "GND_63") (pintype "passive"))
      (node (ref "DD1") (pin "64") (pinfunction "GND_64") (pintype "passive"))
      (node (ref "DD1") (pin "65") (pinfunction "GND_65") (pintype "passive"))
      (node (ref "M20") (pin "2") (pintype "passive"))
      (node (ref "M21") (pin "2") (pintype "passive"))
      (node (ref "R126") (pin "2") (pintype "passive"))
      (node (ref "R127") (pin "2") (pintype "passive"))
      (node (ref "R14") (pin "2") (pintype "passive"))
      (node (ref "X2") (pin "2") (pinfunction "2_2") (pintype "passive"))
      (node (ref "X28") (pin "2") (pinfunction "2_2") (pintype "passive"))
      (node (ref "X29") (pin "2") (pinfunction "2_2") (pintype "passive"))
      (node (ref "X3") (pin "2") (pintype "passive"))
    )
    (net (code "61") (name "/KB_C0") (class "Default")
      (node (ref "DD2") (pin "59") (pinfunction "PD12_59") (pintype "passive"))
      (node (ref "R39") (pin "1") (pintype "passive"))
      (node (ref "SW1") (pin "C1") (pintype "passive"))
    )
    (net (code "62") (name "/KB_C1") (class "Default")
      (node (ref "DD2") (pin "60") (pinfunction "PD13_60") (pintype "passive"))
      (node (ref "R38") (pin "1") (pintype "passive"))
      (node (ref "SW1") (pin "C2") (pintype "passive"))
    )
    (net (code "63") (name "/KB_C2") (class "Default")
      (node (ref "DD2") (pin "61") (pinfunction "PD14_61") (pintype "passive"))
      (node (ref "R37") (pin "1") (pintype "passive"))
      (node (ref "SW1") (pin "C3") (pintype "passive"))
    )
    (net (code "64") (name "/KB_C3") (class "Default")
      (node (ref "DD2") (pin "62") (pinfunction "PD15_62") (pintype "passive"))
      (node (ref "R35") (pin "1") (pintype "passive"))
      (node (ref "SW1") (pin "C4") (pintype "passive"))
    )
    (net (code "65") (name "/KB_R0") (class "Default")
      (node (ref "DD2") (pin "63") (pinfunction "PC6_63") (pintype "passive"))
      (node (ref "SW1") (pin "R1") (pintype "passive"))
    )
    (net (code "66") (name "/KB_R1") (class "Default")
      (node (ref "DD2") (pin "64") (pinfunction "PC7_64") (pintype "passive"))
      (node (ref "SW1") (pin "R2") (pintype "passive"))
    )
    (net (code "67") (name "/KB_R2") (class "Default")
      (node (ref "DD2") (pin "57") (pinfunction "PD10_57") (pintype "passive"))
      (node (ref "SW1") (pin "R3") (pintype "passive"))
    )
    (net (code "68") (name "/KB_R3") (class "Default")
      (node (ref "DD2") (pin "58") (pinfunction "PD11_58") (pintype "passive"))
      (node (ref "SW1") (pin "R4") (pintype "passive"))
    )
    (net (code "69") (name "/LCD_DB4") (class "Default")
      (node (ref "DD2") (pin "15") (pinfunction "PC0_15") (pintype "passive"))
      (node (ref "LCD1") (pin "DB4") (pinfunction "DB4_DB4") (pintype "passive"))
    )
    (net (code "70") (name "/LCD_DB5") (class "Default")
      (node (ref "DD2") (pin "16") (pinfunction "PC1_16") (pintype "passive"))
      (node (ref "LCD1") (pin "DB5") (pinfunction "DB5_DB5") (pintype "passive"))
    )
    (net (code "71") (name "/LCD_DB6") (class "Default")
      (node (ref "DD2") (pin "17") (pinfunction "PC2_17") (pintype "passive"))
      (node (ref "LCD1") (pin "DB6") (pinfunction "DB6_DB6") (pintype "passive"))
    )
    (net (code "72") (name "/LCD_DB7") (class "Default")
      (node (ref "DD2") (pin "18") (pinfunction "PC3_18") (pintype "passive"))
      (node (ref "LCD1") (pin "DB7") (pinfunction "DB7_DB7") (pintype "passive"))
    )
    (net (code "73") (name "/LCD_E") (class "Default")
      (node (ref "DD2") (pin "4") (pinfunction "PE5_4") (pintype "passive"))
      (node (ref "LCD1") (pin "E") (pinfunction "E_E") (pintype "passive"))
      (node (ref "R8") (pin "1") (pintype "passive"))
    )
    (net (code "74") (name "/LCD_LED_ON") (class "Default")
      (node (ref "DD2") (pin "5") (pinfunction "PE6_5") (pintype "passive"))
      (node (ref "M1") (pin "1") (pintype "passive"))
      (node (ref "R12") (pin "1") (pintype "passive"))
    )
    (net (code "75") (name "/LCD_RS") (class "Default")
      (node (ref "DD2") (pin "2") (pinfunction "PE3_2") (pintype "passive"))
      (node (ref "LCD1") (pin "RS") (pinfunction "RS_RS") (pintype "passive"))
    )
    (net (code "76") (name "/LCD_RW") (class "Default")
      (node (ref "DD2") (pin "3") (pinfunction "PE4_3") (pintype "passive"))
      (node (ref "LCD1") (pin "RW") (pinfunction "RW_RW") (pintype "passive"))
    )
    (net (code "77") (name "/MCU_AMP_IN") (class "Default")
      (node (ref "DD2") (pin "29") (pinfunction "PA4_29") (pintype "passive"))
    )
    (net (code "78") (name "/MIC_OUT") (class "Default")
      (node (ref "DD2") (pin "34") (pinfunction "PC5_34") (pintype "passive"))
    )
    (net (code "79") (name "/NRF_CE") (class "Default")
      (node (ref "DD2") (pin "55") (pinfunction "PD8_55") (pintype "passive"))
      (node (ref "R43") (pin "1") (pintype "passive"))
      (node (ref "RF1") (pin "3") (pinfunction "CE_3") (pintype "passive"))
    )
    (net (code "80") (name "/NRF_CSN") (class "Default")
      (node (ref "DD2") (pin "51") (pinfunction "PB12_51") (pintype "passive"))
      (node (ref "R42") (pin "2") (pintype "passive"))
      (node (ref "RF1") (pin "4") (pinfunction "CSN_4") (pintype "passive"))
    )
    (net (code "81") (name "/NRF_IRQ") (class "Default")
      (node (ref "DD2") (pin "56") (pinfunction "PD9_56") (pintype "passive"))
      (node (ref "RF1") (pin "8") (pinfunction "IRQ_8") (pintype "passive"))
    )
    (net (code "82") (name "/NRF_MISO") (class "Default")
      (node (ref "DD2") (pin "53") (pinfunction "PB14_53") (pintype "passive"))
      (node (ref "RF1") (pin "7") (pinfunction "MISO_7") (pintype "passive"))
    )
    (net (code "83") (name "/NRF_MOSI") (class "Default")
      (node (ref "DD2") (pin "54") (pinfunction "PB15_54") (pintype "passive"))
      (node (ref "RF1") (pin "6") (pinfunction "MOSI_6") (pintype "passive"))
    )
    (net (code "84") (name "/NRF_SCK") (class "Default")
      (node (ref "DD2") (pin "52") (pinfunction "PB13_52") (pintype "passive"))
      (node (ref "RF1") (pin "5") (pinfunction "SCK_5") (pintype "passive"))
    )
    (net (code "85") (name "/OSC_IN") (class "Default")
      (node (ref "C5") (pin "2") (pintype "passive"))
      (node (ref "DD2") (pin "12") (pinfunction "OSC_IN_12") (pintype "passive"))
      (node (ref "Q1") (pin "1") (pintype "passive"))
    )
    (net (code "86") (name "/OSC_OUT") (class "Default")
      (node (ref "C6") (pin "2") (pintype "passive"))
      (node (ref "DD2") (pin "13") (pinfunction "OSC_OUT_13") (pintype "passive"))
      (node (ref "Q1") (pin "2") (pintype "passive"))
    )
    (net (code "87") (name "/SD_CLK") (class "Default")
      (node (ref "DD2") (pin "80") (pinfunction "PC12_80") (pintype "passive"))
      (node (ref "X16") (pin "SD_CLK") (pinfunction "CLK_SD_CLK") (pintype "passive"))
    )
    (net (code "88") (name "/SD_CMD") (class "Default")
      (node (ref "DD2") (pin "83") (pinfunction "PD2_83") (pintype "passive"))
      (node (ref "R28") (pin "1") (pintype "passive"))
      (node (ref "X16") (pin "SD_CMD") (pinfunction "CMD/DI_SD_CMD") (pintype "passive"))
    )
    (net (code "89") (name "/SD_DAT0") (class "Default")
      (node (ref "DD2") (pin "65") (pinfunction "PC8_65") (pintype "passive"))
      (node (ref "R34") (pin "1") (pintype "passive"))
      (node (ref "X16") (pin "SD_DAT0") (pinfunction "DAT0/DO_SD_DAT0") (pintype "passive"))
    )
    (net (code "90") (name "/SD_DAT1") (class "Default")
      (node (ref "DD2") (pin "66") (pinfunction "PC9_66") (pintype "passive"))
      (node (ref "R29") (pin "1") (pintype "passive"))
      (node (ref "X16") (pin "SD_DAT1") (pinfunction "DAT1_SD_DAT1") (pintype "passive"))
    )
    (net (code "91") (name "/SD_DAT2") (class "Default")
      (node (ref "DD2") (pin "78") (pinfunction "PC10_78") (pintype "passive"))
      (node (ref "R33") (pin "1") (pintype "passive"))
      (node (ref "X16") (pin "SD_DAT2") (pinfunction "DAT2_SD_DAT2") (pintype "passive"))
    )
    (net (code "92") (name "/SD_DAT3") (class "Default")
      (node (ref "DD2") (pin "79") (pinfunction "PC11_79") (pintype "passive"))
      (node (ref "R30") (pin "1") (pintype "passive"))
      (node (ref "X16") (pin "SD_DAT3") (pinfunction "DAT3/CS_SD_DAT3") (pintype "passive"))
    )
    (net (code "93") (name "/SD_PRES") (class "Default")
      (node (ref "DD2") (pin "77") (pinfunction "PA15_77") (pintype "passive"))
      (node (ref "R31") (pin "1") (pintype "passive"))
      (node (ref "X16") (pin "SD_PRES2") (pintype "passive"))
    )
    (net (code "94") (name "/SET_BAT_SUPPLY_B1") (class "Default")
      (node (ref "X27") (pin "3") (pinfunction "3_3") (pintype "passive"))
    )
    (net (code "95") (name "/SET_BAT_SUPPLY_B2") (class "Default")
      (node (ref "DD2") (pin "38") (pinfunction "PE7_38") (pintype "passive"))
      (node (ref "X29") (pin "3") (pinfunction "3_3") (pintype "passive"))
    )
    (net (code "96") (name "/SIM900_DBG_RX") (class "Default")
      (node (ref "DD1") (pin "28") (pinfunction "DBG_RXD_28") (pintype "passive"))
      (node (ref "R15") (pin "2") (pintype "passive"))
      (node (ref "X5") (pin "2") (pinfunction "2_2") (pintype "passive"))
    )
    (net (code "97") (name "/SIM900_DBG_TX") (class "Default")
      (node (ref "DD1") (pin "27") (pinfunction "DBG_TXD_27") (pintype "passive"))
      (node (ref "X5") (pin "1") (pinfunction "1_1") (pintype "passive"))
    )
    (net (code "98") (name "/SIM900_MIC_KEY") (class "Default")
      (node (ref "DD2") (pin "42") (pinfunction "PE11_42") (pintype "passive"))
    )
    (net (code "99") (name "/SIM900_MIC_MN") (class "Default")
      (node (ref "DD1") (pin "20") (pinfunction "MIC_N_20") (pintype "passive"))
    )
    (net (code "100") (name "/SIM900_MIC_PL") (class "Default")
      (node (ref "DD1") (pin "19") (pinfunction "MIC_P_19") (pintype "passive"))
    )
    (net (code "101") (name "/SIM900_PWR_KEY") (class "Default")
      (node (ref "DD1") (pin "1") (pinfunction "PWRKEY_1") (pintype "passive"))
      (node (ref "DD2") (pin "85") (pinfunction "PD4_85") (pintype "passive"))
      (node (ref "X2") (pin "1") (pinfunction "1_1") (pintype "passive"))
    )
    (net (code "102") (name "/SIM900_RX_MCU_TX") (class "Default")
      (node (ref "DD2") (pin "86") (pinfunction "PD5_86") (pintype "passive"))
      (node (ref "R13") (pin "1") (pintype "passive"))
      (node (ref "X14") (pin "1") (pinfunction "1_1") (pintype "passive"))
    )
    (net (code "103") (name "/SIM900_SPK_PL") (class "Default")
      (node (ref "DD1") (pin "21") (pinfunction "SPK_P_21") (pintype "passive"))
    )
    (net (code "104") (name "/SIM900_TX_MCU_RX") (class "Default")
      (node (ref "DD1") (pin "9") (pinfunction "TXD_9") (pintype "passive"))
      (node (ref "DD2") (pin "87") (pinfunction "PD6_87") (pintype "passive"))
      (node (ref "X14") (pin "2") (pinfunction "2_2") (pintype "passive"))
    )
    (net (code "105") (name "/SIM900_VBAT") (class "Default")
      (node (ref "C24") (pin "1") (pintype "passive"))
      (node (ref "C25") (pin "1") (pintype "passive"))
      (node (ref "DD1") (pin "55") (pinfunction "VBAT_55") (pintype "passive"))
      (node (ref "DD1") (pin "56") (pinfunction "VBAT_56") (pintype "passive"))
      (node (ref "DD1") (pin "57") (pinfunction "VBAT_57") (pintype "passive"))
      (node (ref "M19") (pin "3") (pintype "passive"))
      (node (ref "R116") (pin "1") (pintype "passive"))
    )
    (net (code "106") (name "/SIM900_VBAT_KEY") (class "Default")
      (node (ref "DD2") (pin "82") (pinfunction "PD1_82") (pintype "passive"))
      (node (ref "M20") (pin "1") (pintype "passive"))
      (node (ref "R126") (pin "1") (pintype "passive"))
    )
    (net (code "107") (name "/SIM900_VDD_EXT") (class "Default")
      (node (ref "DD1") (pin "15") (pinfunction "VDD_EXT_15") (pintype "passive"))
      (node (ref "R15") (pin "1") (pintype "passive"))
    )
    (net (code "108") (name "/SIM_CLK") (class "Default")
      (node (ref "DD1") (pin "32") (pinfunction "SIM_CLK_32") (pintype "passive"))
      (node (ref "R23") (pin "2") (pintype "passive"))
    )
    (net (code "109") (name "/SIM_DATA") (class "Default")
      (node (ref "DD1") (pin "31") (pinfunction "SIM_DATA_31") (pintype "passive"))
      (node (ref "R24") (pin "1") (pintype "passive"))
    )
    (net (code "110") (name "/SIM_RES") (class "Default")
      (node (ref "DD1") (pin "33") (pinfunction "SIM_RST_33") (pintype "passive"))
      (node (ref "R25") (pin "2") (pintype "passive"))
    )
    (net (code "111") (name "/SIM_VDD") (class "Default")
      (node (ref "DD1") (pin "30") (pinfunction "SIM_VDD_30") (pintype "passive"))
      (node (ref "X16") (pin "SIM_VDD") (pinfunction "VDD_SIM_VDD") (pintype "passive"))
    )
    (net (code "112") (name "/SOCK_VOLT_PRES_B1") (class "Default")
      (node (ref "X30") (pin "4") (pinfunction "4_4") (pintype "passive"))
    )
    (net (code "113") (name "/SOCK_VOLT_PRES_B2") (class "Default")
      (node (ref "DD2") (pin "68") (pinfunction "PA9_68") (pintype "passive"))
      (node (ref "X31") (pin "4") (pinfunction "4_4") (pintype "passive"))
    )
    (net (code "114") (name "/SOUND_MUTE") (class "Default")
      (node (ref "DD2") (pin "41") (pinfunction "PE10_41") (pintype "passive"))
    )
    (net (code "115") (name "/SOUND_SRC_SEL") (class "Default")
      (node (ref "DD2") (pin "43") (pinfunction "PE12_43") (pintype "passive"))
    )
    (net (code "116") (name "/SWCLK") (class "Default")
      (node (ref "DD2") (pin "76") (pinfunction "PA14_76") (pintype "passive"))
      (node (ref "R32") (pin "2") (pintype "passive"))
      (node (ref "X17") (pin "1") (pinfunction "1_1") (pintype "passive"))
    )
    (net (code "117") (name "/SWDIO") (class "Default")
      (node (ref "DD2") (pin "72") (pinfunction "PA13_72") (pintype "passive"))
      (node (ref "R36") (pin "1") (pintype "passive"))
      (node (ref "X17") (pin "2") (pinfunction "2_2") (pintype "passive"))
    )
    (net (code "118") (name "/Socket supply") (class "Default")
      (node (ref "X18") (pin "+") (pinfunction "+_+") (pintype "passive"))
    )
    (net (code "119") (name "/USB_DM") (class "Default")
      (node (ref "C3") (pin "2") (pintype "passive"))
      (node (ref "DD2") (pin "70") (pinfunction "PA11_70") (pintype "passive"))
      (node (ref "R3") (pin "2") (pintype "passive"))
    )
    (net (code "120") (name "/USB_DP") (class "Default")
      (node (ref "C2") (pin "2") (pintype "passive"))
      (node (ref "DD2") (pin "71") (pinfunction "PA12_71") (pintype "passive"))
      (node (ref "R4") (pin "2") (pintype "passive"))
    )
    (net (code "121") (name "/VBUS") (class "Default")
      (node (ref "DD2") (pin "69") (pinfunction "PA10_69") (pintype "passive"))
      (node (ref "R6") (pin "2") (pintype "passive"))
      (node (ref "R9") (pin "1") (pintype "passive"))
    )
    (net (code "122") (name "/VREF_B1") (class "Default")
      (node (ref "X24") (pin "6") (pinfunction "6_6") (pintype "passive"))
    )
    (net (code "123") (name "/VREF_B2") (class "Default")
      (node (ref "DD2") (pin "21") (pinfunction "VREF+_21") (pintype "passive"))
      (node (ref "X25") (pin "6") (pinfunction "6_6") (pintype "passive"))
    )
    (net (code "124") (name "Net-(DD1-RF_ANT)") (class "Default")
      (node (ref "DD1") (pin "60") (pinfunction "RF_ANT_60") (pintype "passive"))
      (node (ref "X3") (pin "1") (pintype "passive"))
    )
    (net (code "125") (name "Net-(DD1-RXD)") (class "Default")
      (node (ref "DD1") (pin "10") (pinfunction "RXD_10") (pintype "passive"))
      (node (ref "R13") (pin "2") (pintype "passive"))
      (node (ref "R14") (pin "1") (pintype "passive"))
    )
    (net (code "126") (name "Net-(DD2-NRST)") (class "Default")
      (node (ref "C7") (pin "2") (pintype "passive"))
      (node (ref "DD2") (pin "14") (pinfunction "NRST_14") (pintype "passive"))
    )
    (net (code "127") (name "Net-(LCD1-PadLED-)") (class "Default")
      (node (ref "LCD1") (pin "LED-") (pinfunction "LED-_LED-") (pintype "passive"))
      (node (ref "R5") (pin "1") (pintype "passive"))
    )
    (net (code "128") (name "Net-(LCD1-PadV0)") (class "Default")
      (node (ref "LCD1") (pin "V0") (pinfunction "V0_V0") (pintype "passive"))
      (node (ref "R7") (pin "3") (pintype "passive"))
    )
    (net (code "129") (name "Net-(M1-Pad3)") (class "Default")
      (node (ref "M1") (pin "3") (pintype "passive"))
      (node (ref "R5") (pin "2") (pintype "passive"))
    )
    (net (code "130") (name "Net-(M19-Pad1)") (class "Default")
      (node (ref "M19") (pin "1") (pintype "passive"))
      (node (ref "M20") (pin "3") (pintype "passive"))
      (node (ref "R115") (pin "2") (pintype "passive"))
    )
    (net (code "131") (name "Net-(M21-Pad3)") (class "Default")
      (node (ref "M21") (pin "3") (pintype "passive"))
      (node (ref "R116") (pin "2") (pintype "passive"))
    )
    (net (code "132") (name "Net-(R1-Pad1)") (class "Default")
      (node (ref "R1") (pin "1") (pintype "passive"))
      (node (ref "R2") (pin "1") (pintype "passive"))
      (node (ref "R6") (pin "1") (pintype "passive"))
      (node (ref "X1") (pin "+5") (pinfunction "+5_+5") (pintype "passive"))
    )
    (net (code "133") (name "Net-(R1-Pad2)") (class "Default")
      (node (ref "R1") (pin "2") (pintype "passive"))
      (node (ref "R10") (pin "1") (pintype "passive"))
      (node (ref "R4") (pin "1") (pintype "passive"))
      (node (ref "X1") (pin "D+") (pinfunction "D+_D+") (pintype "passive"))
    )
    (net (code "134") (name "Net-(R11-Pad1)") (class "Default")
      (node (ref "R11") (pin "1") (pintype "passive"))
      (node (ref "R2") (pin "2") (pintype "passive"))
      (node (ref "R3") (pin "1") (pintype "passive"))
      (node (ref "X1") (pin "D-") (pinfunction "D-_D-") (pintype "passive"))
    )
    (net (code "135") (name "Net-(R23-Pad1)") (class "Default")
      (node (ref "R23") (pin "1") (pintype "passive"))
      (node (ref "X16") (pin "SIM_CLK") (pinfunction "CLK_SIM_CLK") (pintype "passive"))
    )
    (net (code "136") (name "Net-(X16-DATA)") (class "Default")
      (node (ref "R24") (pin "2") (pintype "passive"))
      (node (ref "X16") (pin "SIM_DATA") (pinfunction "DATA_SIM_DATA") (pintype "passive"))
    )
    (net (code "137") (name "Net-(X16-RES)") (class "Default")
      (node (ref "R25") (pin "1") (pintype "passive"))
      (node (ref "X16") (pin "SIM_RES") (pinfunction "RES_SIM_RES") (pintype "passive"))
    )
    (net (code "138") (name "unconnected-(DD1-ADC-Pad25)") (class "Default")
      (node (ref "DD1") (pin "25") (pinfunction "ADC_25") (pintype "passive"))
    )
    (net (code "139") (name "unconnected-(DD1-CTS-Pad7)") (class "Default")
      (node (ref "DD1") (pin "7") (pinfunction "CTS_7") (pintype "passive"))
    )
    (net (code "140") (name "unconnected-(DD1-DCD-Pad5)") (class "Default")
      (node (ref "DD1") (pin "5") (pinfunction "DCD_5") (pintype "passive"))
    )
    (net (code "141") (name "unconnected-(DD1-DISP_CLK-Pad11)") (class "Default")
      (node (ref "DD1") (pin "11") (pinfunction "DISP_CLK_11") (pintype "passive"))
    )
    (net (code "142") (name "unconnected-(DD1-DISP_CS-Pad14)") (class "Default")
      (node (ref "DD1") (pin "14") (pinfunction "DISP_CS_14") (pintype "passive"))
    )
    (net (code "143") (name "unconnected-(DD1-DISP_DATA-Pad12)") (class "Default")
      (node (ref "DD1") (pin "12") (pinfunction "DISP_DATA_12") (pintype "passive"))
    )
    (net (code "144") (name "unconnected-(DD1-DISP_D{slash}C-Pad13)") (class "Default")
      (node (ref "DD1") (pin "13") (pinfunction "DISP_D/C_13") (pintype "passive"))
    )
    (net (code "145") (name "unconnected-(DD1-GPIO1{slash}KBR4-Pad40)") (class "Default")
      (node (ref "DD1") (pin "40") (pinfunction "GPIO1/KBR4_40") (pintype "passive"))
    )
    (net (code "146") (name "unconnected-(DD1-GPIO2{slash}KBR3-Pad41)") (class "Default")
      (node (ref "DD1") (pin "41") (pinfunction "GPIO2/KBR3_41") (pintype "passive"))
    )
    (net (code "147") (name "unconnected-(DD1-GPIO3{slash}KBR2-Pad42)") (class "Default")
      (node (ref "DD1") (pin "42") (pinfunction "GPIO3/KBR2_42") (pintype "passive"))
    )
    (net (code "148") (name "unconnected-(DD1-GPIO4{slash}KBR1-Pad43)") (class "Default")
      (node (ref "DD1") (pin "43") (pinfunction "GPIO4/KBR1_43") (pintype "passive"))
    )
    (net (code "149") (name "unconnected-(DD1-GPIO5{slash}KBR0-Pad44)") (class "Default")
      (node (ref "DD1") (pin "44") (pinfunction "GPIO5/KBR0_44") (pintype "passive"))
    )
    (net (code "150") (name "unconnected-(DD1-GPIO6{slash}KBC4-Pad47)") (class "Default")
      (node (ref "DD1") (pin "47") (pinfunction "GPIO6/KBC4_47") (pintype "passive"))
    )
    (net (code "151") (name "unconnected-(DD1-GPIO7{slash}KBC3-Pad48)") (class "Default")
      (node (ref "DD1") (pin "48") (pinfunction "GPIO7/KBC3_48") (pintype "passive"))
    )
    (net (code "152") (name "unconnected-(DD1-GPIO8{slash}KBC2-Pad49)") (class "Default")
      (node (ref "DD1") (pin "49") (pinfunction "GPIO8/KBC2_49") (pintype "passive"))
    )
    (net (code "153") (name "unconnected-(DD1-GPIO9{slash}KBC1-Pad50)") (class "Default")
      (node (ref "DD1") (pin "50") (pinfunction "GPIO9/KBC1_50") (pintype "passive"))
    )
    (net (code "154") (name "unconnected-(DD1-GPIO10{slash}KBC0-Pad51)") (class "Default")
      (node (ref "DD1") (pin "51") (pinfunction "GPIO10/KBC0_51") (pintype "passive"))
    )
    (net (code "155") (name "unconnected-(DD1-GPIO11-Pad67)") (class "Default")
      (node (ref "DD1") (pin "67") (pinfunction "GPIO11_67") (pintype "passive"))
    )
    (net (code "156") (name "unconnected-(DD1-GPIO12-Pad68)") (class "Default")
      (node (ref "DD1") (pin "68") (pinfunction "GPIO12_68") (pintype "passive"))
    )
    (net (code "157") (name "unconnected-(DD1-LINEIN_L-Pad24)") (class "Default")
      (node (ref "DD1") (pin "24") (pinfunction "LINEIN_L_24") (pintype "passive"))
    )
    (net (code "158") (name "unconnected-(DD1-LINEIN_R-Pad23)") (class "Default")
      (node (ref "DD1") (pin "23") (pinfunction "LINEIN_R_23") (pintype "passive"))
    )
    (net (code "159") (name "unconnected-(DD1-NC-Pad2)") (class "Default")
      (node (ref "DD1") (pin "2") (pinfunction "NC_2") (pintype "passive"))
    )
    (net (code "160") (name "unconnected-(DD1-NC-Pad6)") (class "Default")
      (node (ref "DD1") (pin "6") (pinfunction "NC_6") (pintype "passive"))
    )
    (net (code "161") (name "unconnected-(DD1-NETLIGHT-Pad52)") (class "Default")
      (node (ref "DD1") (pin "52") (pinfunction "NETLIGHT_52") (pintype "passive"))
    )
    (net (code "162") (name "unconnected-(DD1-NRESET-Pad16)") (class "Default")
      (node (ref "DD1") (pin "16") (pinfunction "NRESET_16") (pintype "passive"))
    )
    (net (code "163") (name "unconnected-(DD1-PWM1-Pad35)") (class "Default")
      (node (ref "DD1") (pin "35") (pinfunction "PWM1_35") (pintype "passive"))
    )
    (net (code "164") (name "unconnected-(DD1-PWM2-Pad36)") (class "Default")
      (node (ref "DD1") (pin "36") (pinfunction "PWM2_36") (pintype "passive"))
    )
    (net (code "165") (name "unconnected-(DD1-RI-Pad4)") (class "Default")
      (node (ref "DD1") (pin "4") (pinfunction "RI_4") (pintype "passive"))
    )
    (net (code "166") (name "unconnected-(DD1-RTS-Pad8)") (class "Default")
      (node (ref "DD1") (pin "8") (pinfunction "RTS_8") (pintype "passive"))
    )
    (net (code "167") (name "unconnected-(DD1-SCL-Pad38)") (class "Default")
      (node (ref "DD1") (pin "38") (pinfunction "SCL_38") (pintype "passive"))
    )
    (net (code "168") (name "unconnected-(DD1-SDA-Pad37)") (class "Default")
      (node (ref "DD1") (pin "37") (pinfunction "SDA_37") (pintype "passive"))
    )
    (net (code "169") (name "unconnected-(DD1-SIM_PRESENT-Pad34)") (class "Default")
      (node (ref "DD1") (pin "34") (pinfunction "SIM_PRESENT_34") (pintype "passive"))
    )
    (net (code "170") (name "unconnected-(DD1-SPK_N-Pad22)") (class "Default")
      (node (ref "DD1") (pin "22") (pinfunction "SPK_N_22") (pintype "passive"))
    )
    (net (code "171") (name "unconnected-(DD1-STATUS-Pad66)") (class "Default")
      (node (ref "DD1") (pin "66") (pinfunction "STATUS_66") (pintype "passive"))
    )
    (net (code "172") (name "unconnected-(DD1-VRTC-Pad26)") (class "Default")
      (node (ref "DD1") (pin "26") (pinfunction "VRTC_26") (pintype "passive"))
    )
    (net (code "173") (name "unconnected-(DD2-NC-Pad73)") (class "Default")
      (node (ref "DD2") (pin "73") (pinfunction "NC_73") (pintype "passive"))
    )
    (net (code "174") (name "unconnected-(DD2-PA3-Pad26)") (class "Default")
      (node (ref "DD2") (pin "26") (pinfunction "PA3_26") (pintype "passive"))
    )
    (net (code "175") (name "unconnected-(DD2-PB0-Pad35)") (class "Default")
      (node (ref "DD2") (pin "35") (pinfunction "PB0_35") (pintype "passive"))
    )
    (net (code "176") (name "unconnected-(DD2-PB1-Pad36)") (class "Default")
      (node (ref "DD2") (pin "36") (pinfunction "PB1_36") (pintype "passive"))
    )
    (net (code "177") (name "unconnected-(DD2-PB8-Pad95)") (class "Default")
      (node (ref "DD2") (pin "95") (pinfunction "PB8_95") (pintype "passive"))
    )
    (net (code "178") (name "unconnected-(DD2-PC13-TAMPER-RTC-Pad7)") (class "Default")
      (node (ref "DD2") (pin "7") (pinfunction "PC13-TAMPER-RTC_7") (pintype "passive"))
    )
    (net (code "179") (name "unconnected-(DD2-PC14-OSC32_IN-Pad8)") (class "Default")
      (node (ref "DD2") (pin "8") (pinfunction "PC14-OSC32_IN_8") (pintype "passive"))
    )
    (net (code "180") (name "unconnected-(DD2-PC15-OSC32_OUT-Pad9)") (class "Default")
      (node (ref "DD2") (pin "9") (pinfunction "PC15-OSC32_OUT_9") (pintype "passive"))
    )
    (net (code "181") (name "unconnected-(DD2-PD3-Pad84)") (class "Default")
      (node (ref "DD2") (pin "84") (pinfunction "PD3_84") (pintype "passive"))
    )
    (net (code "182") (name "unconnected-(DD2-PE8-Pad39)") (class "Default")
      (node (ref "DD2") (pin "39") (pinfunction "PE8_39") (pintype "passive"))
    )
    (net (code "183") (name "unconnected-(DD2-PE9-Pad40)") (class "Default")
      (node (ref "DD2") (pin "40") (pinfunction "PE9_40") (pintype "passive"))
    )
    (net (code "184") (name "unconnected-(LCD1-PadDB0)") (class "Default")
      (node (ref "LCD1") (pin "DB0") (pinfunction "DB0_DB0") (pintype "passive"))
    )
    (net (code "185") (name "unconnected-(LCD1-PadDB1)") (class "Default")
      (node (ref "LCD1") (pin "DB1") (pinfunction "DB1_DB1") (pintype "passive"))
    )
    (net (code "186") (name "unconnected-(LCD1-PadDB2)") (class "Default")
      (node (ref "LCD1") (pin "DB2") (pinfunction "DB2_DB2") (pintype "passive"))
    )
    (net (code "187") (name "unconnected-(LCD1-PadDB3)") (class "Default")
      (node (ref "LCD1") (pin "DB3") (pinfunction "DB3_DB3") (pintype "passive"))
    )
    (net (code "188") (name "unconnected-(X1-PadID)") (class "Default")
      (node (ref "X1") (pin "ID") (pinfunction "ID_ID") (pintype "passive"))
    )
    (net (code "189") (name "unconnected-(X16-VPP-PadSIM_VPP)") (class "Default")
      (node (ref "X16") (pin "SIM_VPP") (pinfunction "VPP_SIM_VPP") (pintype "passive"))
    )
  )
)
